# Headphone-Amplifier-ClassAB-13x7.net
KiCad netlist of a schematic drawn in EAGLE
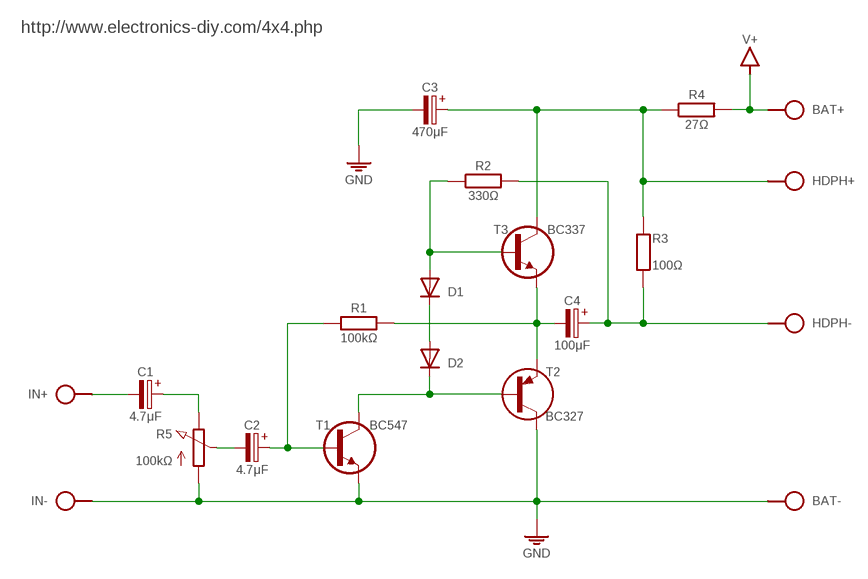
[diagram p0: schematic, sheet 1]

(export (version "E")
  (design (tool "Eeschema 10.0.6"))
  (components
    (comp (ref "BAT")
      (value "SPAD+-+-")
      (footprint "eagle-import:SPAD+-")
      (libsource (lib "eagle-import") (part "SPAD+-+-"))
    )
    (comp (ref "C1")
      (value "4.7μF")
      (footprint "eagle-import:E2,5-4")
      (libsource (lib "eagle-import") (part "CPOLE2,5-4"))
    )
    (comp (ref "C2")
      (value "4.7μF")
      (footprint "eagle-import:E2,5-4")
      (libsource (lib "eagle-import") (part "CPOLE2,5-4"))
    )
    (comp (ref "C3")
      (value "470μF")
      (footprint "eagle-import:E5-6")
      (libsource (lib "eagle-import") (part "CPOLE5-6"))
    )
    (comp (ref "C4")
      (value "100μF")
      (footprint "eagle-import:E5-4")
      (libsource (lib "eagle-import") (part "CPOLE5-4"))
    )
    (comp (ref "D1")
      (value "1N414834-5V")
      (footprint "eagle-import:DO34-5V")
      (libsource (lib "eagle-import") (part "1N414834-5V"))
    )
    (comp (ref "D2")
      (value "1N414834-5V")
      (footprint "eagle-import:DO34-5V")
      (libsource (lib "eagle-import") (part "1N414834-5V"))
    )
    (comp (ref "HDPH")
      (value "SPAD+--+")
      (footprint "eagle-import:SPAD-+")
      (libsource (lib "eagle-import") (part "SPAD+--+"))
    )
    (comp (ref "IN")
      (value "SPAD+--+")
      (footprint "eagle-import:SPAD-+")
      (libsource (lib "eagle-import") (part "SPAD+--+"))
    )
    (comp (ref "R1")
      (value "100kΩ")
      (footprint "eagle-import:0202_7")
      (libsource (lib "eagle-import") (part "R-H0202/7"))
    )
    (comp (ref "R2")
      (value "330Ω")
      (footprint "eagle-import:0202_7")
      (libsource (lib "eagle-import") (part "R-H0202/7"))
    )
    (comp (ref "R3")
      (value "100Ω")
      (footprint "eagle-import:0202_7")
      (libsource (lib "eagle-import") (part "R0202/7"))
    )
    (comp (ref "R4")
      (value "27Ω")
      (footprint "eagle-import:0204V")
      (libsource (lib "eagle-import") (part "R-H-V-X"))
    )
    (comp (ref "R5")
      (value "100kΩ")
      (footprint "eagle-import:CONN-3P")
      (libsource (lib "eagle-import") (part "POT-3P"))
    )
    (comp (ref "T1")
      (value "BC547")
      (footprint "eagle-import:TO92-CBE")
      (libsource (lib "eagle-import") (part "BC547CBE"))
    )
    (comp (ref "T2")
      (value "BC327")
      (footprint "eagle-import:TO92")
      (libsource (lib "eagle-import") (part "BC327"))
    )
    (comp (ref "T3")
      (value "BC337")
      (footprint "eagle-import:TO92-CBE")
      (libsource (lib "eagle-import") (part "BC337CBE"))
    )
  )
  (nets
    (net (code "1") (name "GND") (class "Default")
      (node (ref "BAT") (pin "1") (pinfunction "P$1_1") (pintype "passive"))
      (node (ref "C3") (pin "-") (pinfunction "-_-") (pintype "passive"))
      (node (ref "IN") (pin "1") (pinfunction "P$1_1") (pintype "passive"))
      (node (ref "R5") (pin "1") (pinfunction "A_1") (pintype "passive"))
      (node (ref "T1") (pin "E") (pinfunction "E_E") (pintype "passive"))
      (node (ref "T2") (pin "1") (pinfunction "C_1") (pintype "passive"))
    )
    (net (code "2") (name "Net-(C2-Pad+)") (class "Default")
      (node (ref "C2") (pin "+") (pinfunction "+_+") (pintype "passive"))
      (node (ref "R1") (pin "1") (pinfunction "1_1") (pintype "passive"))
      (node (ref "T1") (pin "B") (pinfunction "B_B") (pintype "passive"))
    )
    (net (code "3") (name "Net-(D1-PadA)") (class "Default")
      (node (ref "D1") (pin "A") (pinfunction "A_A") (pintype "passive"))
      (node (ref "R2") (pin "1") (pinfunction "1_1") (pintype "passive"))
      (node (ref "T3") (pin "B") (pinfunction "B_B") (pintype "passive"))
    )
    (net (code "4") (name "Net-(D1-PadC)") (class "Default")
      (node (ref "D1") (pin "C") (pinfunction "C_C") (pintype "passive"))
      (node (ref "D2") (pin "A") (pinfunction "A_A") (pintype "passive"))
    )
    (net (code "5") (name "Net-(HDPHA-P$1)") (class "Default")
      (node (ref "C3") (pin "+") (pinfunction "+_+") (pintype "passive"))
      (node (ref "HDPH") (pin "2") (pinfunction "P$1_2") (pintype "passive"))
      (node (ref "R3") (pin "2") (pinfunction "1_2") (pintype "passive"))
      (node (ref "R4") (pin "2") (pinfunction "1_2") (pintype "passive"))
      (node (ref "T3") (pin "C") (pinfunction "C_C") (pintype "passive"))
    )
    (net (code "6") (name "Net-(HDPHB-P$1)") (class "Default")
      (node (ref "C4") (pin "+") (pinfunction "+_+") (pintype "passive"))
      (node (ref "HDPH") (pin "1") (pinfunction "P$1_1") (pintype "passive"))
      (node (ref "R2") (pin "2") (pinfunction "2_2") (pintype "passive"))
      (node (ref "R3") (pin "1") (pinfunction "2_1") (pintype "passive"))
    )
    (net (code "7") (name "Net-(INA-P$1)") (class "Default")
      (node (ref "C1") (pin "-") (pinfunction "-_-") (pintype "passive"))
      (node (ref "IN") (pin "2") (pinfunction "P$1_2") (pintype "passive"))
    )
    (net (code "8") (name "Net-(R5-E)") (class "Default")
      (node (ref "C1") (pin "+") (pinfunction "+_+") (pintype "passive"))
      (node (ref "R5") (pin "3") (pinfunction "E_3") (pintype "passive"))
    )
    (net (code "9") (name "Net-(R5-S)") (class "Default")
      (node (ref "C2") (pin "-") (pinfunction "-_-") (pintype "passive"))
      (node (ref "R5") (pin "2") (pinfunction "S_2") (pintype "passive"))
    )
    (net (code "10") (name "Net-(T2-B)") (class "Default")
      (node (ref "D2") (pin "C") (pinfunction "C_C") (pintype "passive"))
      (node (ref "T1") (pin "C") (pinfunction "C_C") (pintype "passive"))
      (node (ref "T2") (pin "2") (pinfunction "B_2") (pintype "passive"))
    )
    (net (code "11") (name "Net-(T2-E)") (class "Default")
      (node (ref "C4") (pin "-") (pinfunction "-_-") (pintype "passive"))
      (node (ref "R1") (pin "2") (pinfunction "2_2") (pintype "passive"))
      (node (ref "T2") (pin "3") (pinfunction "E_3") (pintype "passive"))
      (node (ref "T3") (pin "E") (pinfunction "E_E") (pintype "passive"))
    )
    (net (code "12") (name "V+") (class "Default")
      (node (ref "BAT") (pin "2") (pinfunction "P$1_2") (pintype "passive"))
      (node (ref "R4") (pin "1") (pinfunction "2_1") (pintype "passive"))
    )
  )
)
